# SCH_clock1_2025-09-25.net
KiCad netlist of a schematic drawn in EasyEDA
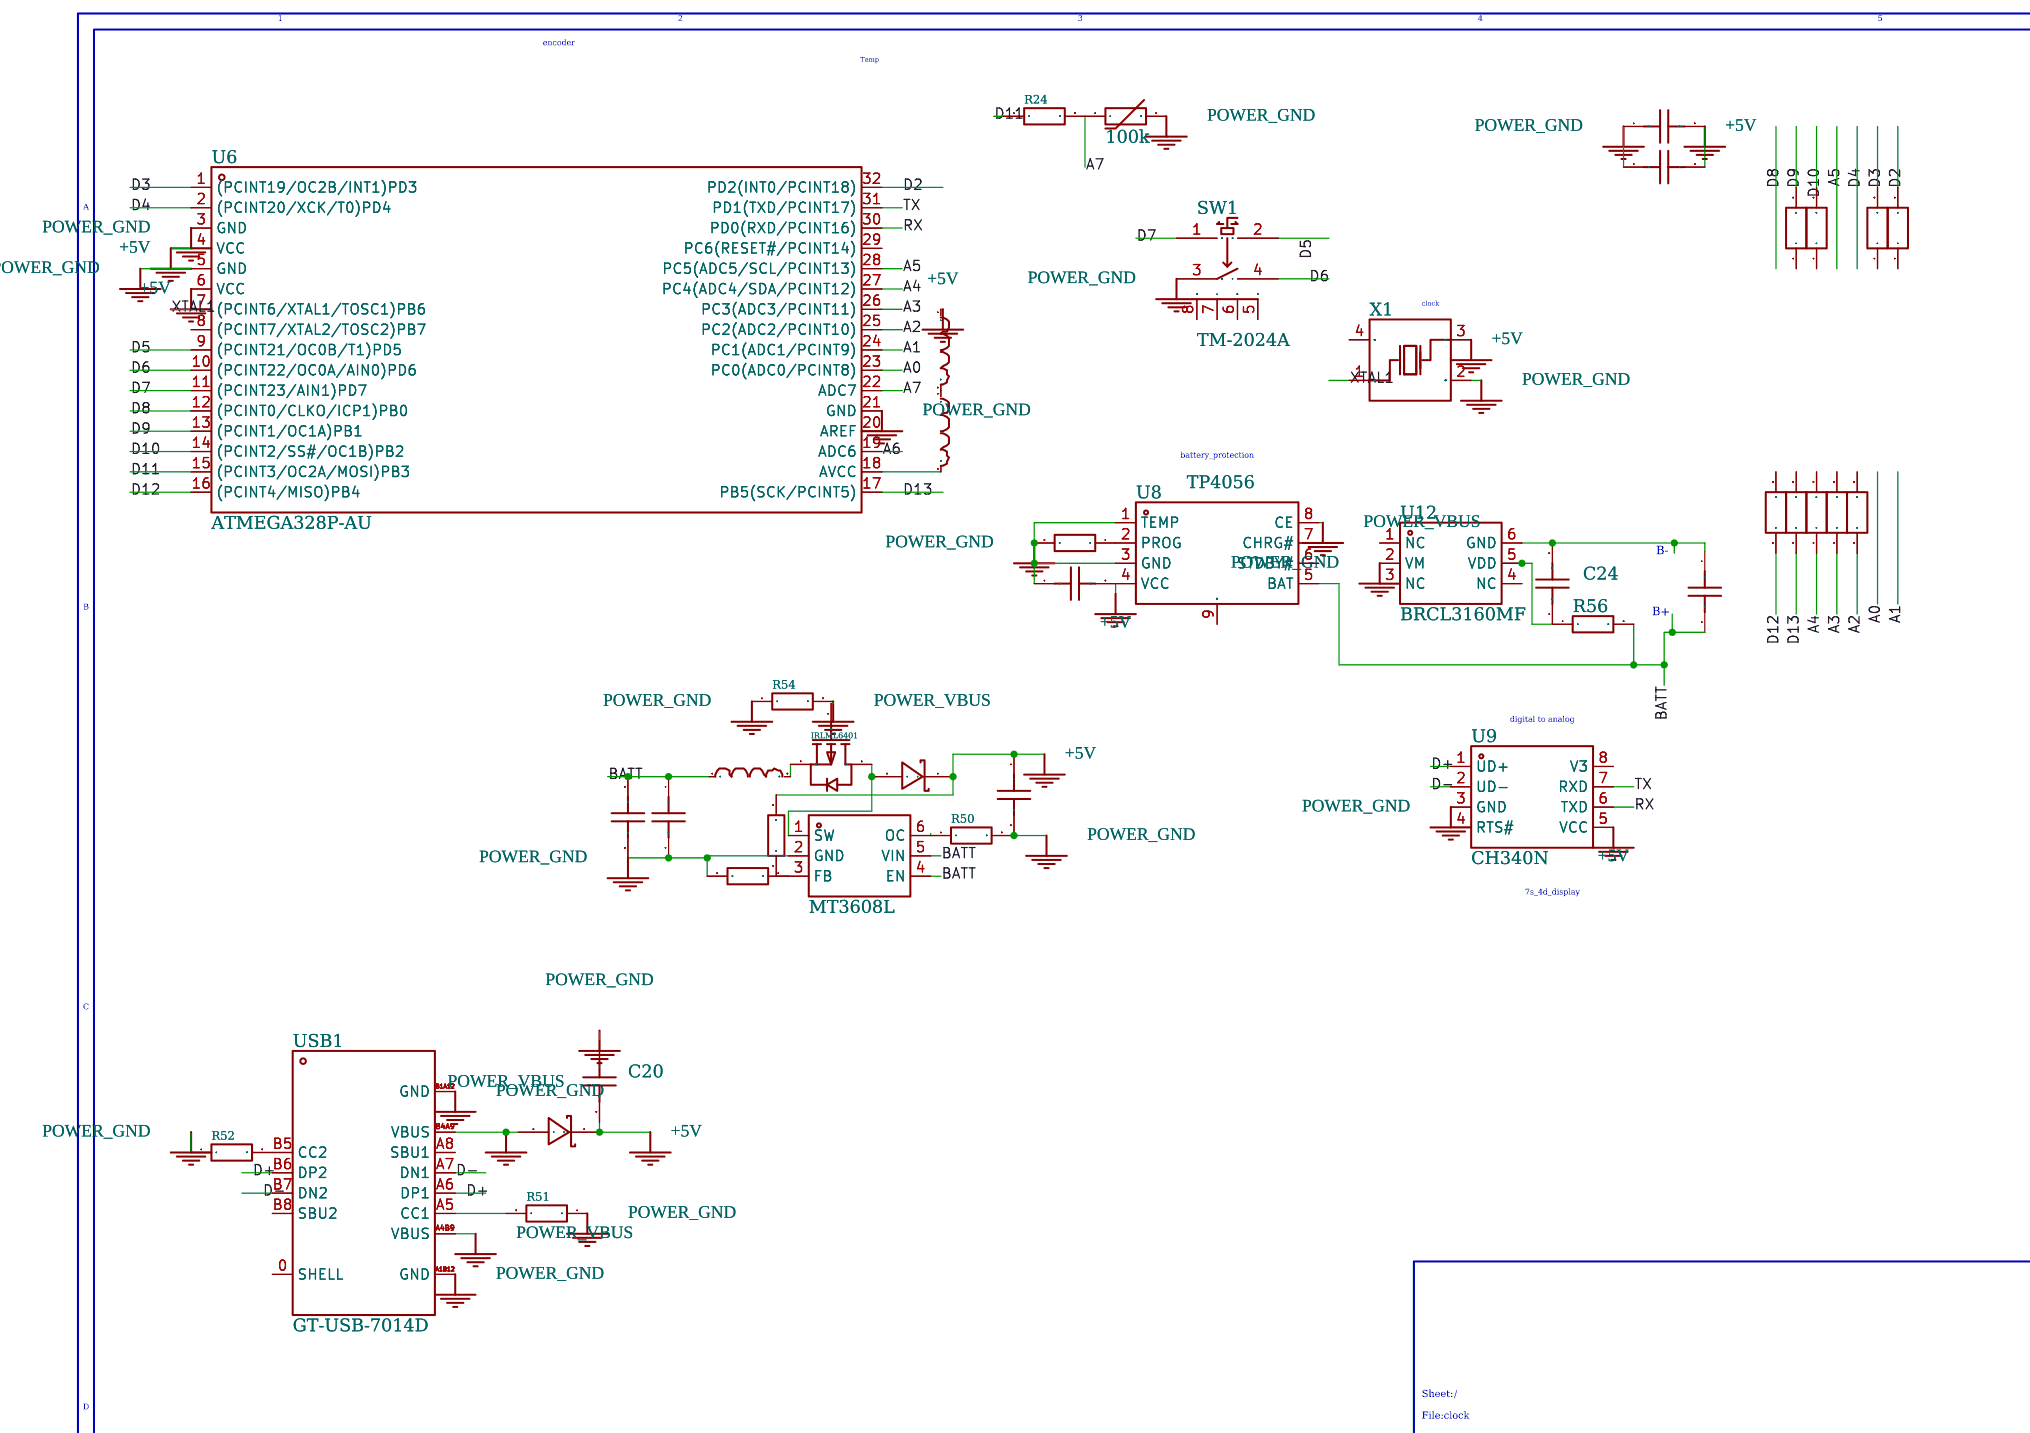
[diagram p0: schematic sheet]

(export (version "E")
  (design (tool "Eeschema 10.0.6"))
  (components
    (comp (ref "C15")
      (value "4.7uF")
      (fields
        (field (name "Manufacturer Part") "CL05A475MQ5NRNC")
        (field (name "Manufacturer") "SAMSUNG(三星)")
      )
      (libsource (lib "") (part "Unknown_300_-375"))
    )
    (comp (ref "C16")
      (value "4.7uF")
      (fields
        (field (name "Manufacturer Part") "CL05A475MQ5NRNC")
        (field (name "Manufacturer") "SAMSUNG(三星)")
      )
      (libsource (lib "") (part "Unknown_320_-375"))
    )
    (comp (ref "C19")
      (value "4.7uF")
      (fields
        (field (name "Manufacturer Part") "CL05A475MQ5NRNC")
        (field (name "Manufacturer") "SAMSUNG(三星)")
      )
      (libsource (lib "") (part "Unknown_520_-490"))
    )
    (comp (ref "C20")
      (value "4.7uF")
      (fields
        (field (name "Manufacturer Part") "CL05A475MQ5NRNC")
        (field (name "Manufacturer") "SAMSUNG(三星)")
      )
      (libsource (lib "") (part "Unknown_286_-245"))
    )
    (comp (ref "C21")
      (value "4.7uF")
      (fields
        (field (name "Manufacturer Part") "CL05A475MQ5NRNC")
        (field (name "Manufacturer") "SAMSUNG(三星)")
      )
      (libsource (lib "") (part "Unknown_490_-386"))
    )
    (comp (ref "C24")
      (value "100nF")
      (fields
        (field (name "Manufacturer Part") "FCC0402B104K160AT")
        (field (name "Manufacturer") "FOJAN(富捷)")
      )
      (libsource (lib "") (part "Unknown_755_-490"))
    )
    (comp (ref "C25")
      (value "4.7uF")
      (fields
        (field (name "Manufacturer Part") "CL05A475MQ5NRNC")
        (field (name "Manufacturer") "SAMSUNG(三星)")
      )
      (libsource (lib "") (part "Unknown_810_-715"))
    )
    (comp (ref "C27")
      (value "4.7uF")
      (fields
        (field (name "Manufacturer Part") "CL05A475MQ5NRNC")
        (field (name "Manufacturer") "SAMSUNG(三星)")
      )
      (libsource (lib "") (part "Unknown_810_-695"))
    )
    (comp (ref "C28")
      (value "4.7uF")
      (fields
        (field (name "Manufacturer Part") "CL05A475MQ5NRNC")
        (field (name "Manufacturer") "SAMSUNG(三星)")
      )
      (libsource (lib "") (part "Unknown_830_-486"))
    )
    (comp (ref "D5")
      (value "DSK34")
      (fields (field (name "Manufacturer") "MDD(辰达半导体)"))
      (libsource (lib "") (part "Unknown_440_-395"))
    )
    (comp (ref "D6")
      (value "DSK34")
      (fields (field (name "Manufacturer") "MDD(辰达半导体)"))
      (libsource (lib "") (part "Unknown_266_-220"))
    )
    (comp (ref "L3")
      (value "4.7uH")
      (fields (field (name "Manufacturer Part") "CMI321609U4R7KT") (field (name "Manufacturer") "FH(风华)"))
      (libsource (lib "") (part "Unknown_360_-395"))
    )
    (comp (ref "L5")
      (value "4.7uH")
      (fields (field (name "Manufacturer Part") "CMI321609U4R7KT") (field (name "Manufacturer") "FH(风华)"))
      (libsource (lib "") (part "Unknown_454_-565"))
    )
    (comp (ref "L6")
      (value "4.7uH")
      (fields (field (name "Manufacturer Part") "CMI321609U4R7KT") (field (name "Manufacturer") "FH(风华)"))
      (libsource (lib "") (part "Unknown_454_-605"))
    )
    (comp (ref "Q1")
      (value "IRLML6401")
      (fields (field (name "Manufacturer") "Hottech(合科泰)"))
      (libsource (lib "") (part "Unknown_400_-401"))
    )
    (comp (ref "R22")
      (value "100k")
      (fields (field (name "Manufacturer Part") "NCP03WF104F05RL") (field (name "Manufacturer") "muRata(村田)"))
      (libsource (lib "") (part "Unknown_545_-720"))
    )
    (comp (ref "R24")
      (value "100kΩ")
      (fields
        (field (name "Manufacturer Part") "0402WGF1003TCE")
        (field (name "Manufacturer") "UNI-ROYAL(厚声)")
      )
      (libsource (lib "") (part "Unknown_505_-720"))
    )
    (comp (ref "R39")
      (value "1kΩ")
      (fields (field (name "Manufacturer Part") "FRC0603F1001TS") (field (name "Manufacturer") "FOJAN(富捷)"))
      (libsource (lib "") (part "Unknown_875_-665"))
    )
    (comp (ref "R40")
      (value "1kΩ")
      (fields (field (name "Manufacturer Part") "FRC0603F1001TS") (field (name "Manufacturer") "FOJAN(富捷)"))
      (libsource (lib "") (part "Unknown_915_-665"))
    )
    (comp (ref "R41")
      (value "1kΩ")
      (fields (field (name "Manufacturer Part") "FRC0603F1001TS") (field (name "Manufacturer") "FOJAN(富捷)"))
      (libsource (lib "") (part "Unknown_885_-665"))
    )
    (comp (ref "R42")
      (value "1kΩ")
      (fields (field (name "Manufacturer Part") "FRC0603F1001TS") (field (name "Manufacturer") "FOJAN(富捷)"))
      (libsource (lib "") (part "Unknown_905_-525"))
    )
    (comp (ref "R43")
      (value "1kΩ")
      (fields (field (name "Manufacturer Part") "FRC0603F1001TS") (field (name "Manufacturer") "FOJAN(富捷)"))
      (libsource (lib "") (part "Unknown_895_-525"))
    )
    (comp (ref "R44")
      (value "1kΩ")
      (fields (field (name "Manufacturer Part") "FRC0603F1001TS") (field (name "Manufacturer") "FOJAN(富捷)"))
      (libsource (lib "") (part "Unknown_925_-665"))
    )
    (comp (ref "R45")
      (value "1kΩ")
      (fields (field (name "Manufacturer Part") "FRC0603F1001TS") (field (name "Manufacturer") "FOJAN(富捷)"))
      (libsource (lib "") (part "Unknown_875_-525"))
    )
    (comp (ref "R46")
      (value "1kΩ")
      (fields (field (name "Manufacturer Part") "FRC0603F1001TS") (field (name "Manufacturer") "FOJAN(富捷)"))
      (libsource (lib "") (part "Unknown_865_-525"))
    )
    (comp (ref "R48")
      (value "2.4kΩ")
      (fields
        (field (name "Manufacturer Part") "0402WGF2401TCE")
        (field (name "Manufacturer") "UNI-ROYAL(厚声)")
      )
      (libsource (lib "") (part "Unknown_520_-510"))
    )
    (comp (ref "R49")
      (value "2.4kΩ")
      (fields
        (field (name "Manufacturer Part") "0402WGF2401TCE")
        (field (name "Manufacturer") "UNI-ROYAL(厚声)")
      )
      (libsource (lib "") (part "Unknown_359_-346"))
    )
    (comp (ref "R50")
      (value "100kΩ")
      (fields
        (field (name "Manufacturer Part") "0402WGF1003TCE")
        (field (name "Manufacturer") "UNI-ROYAL(厚声)")
      )
      (libsource (lib "") (part "Unknown_469_-366"))
    )
    (comp (ref "R51")
      (value "5.1kΩ")
      (fields
        (field (name "Manufacturer Part") "0402WGF5101TCE")
        (field (name "Manufacturer") "UNI-ROYAL(厚声)")
      )
      (libsource (lib "") (part "Unknown_260_-180"))
    )
    (comp (ref "R52")
      (value "5.1kΩ")
      (fields
        (field (name "Manufacturer Part") "0402WGF5101TCE")
        (field (name "Manufacturer") "UNI-ROYAL(厚声)")
      )
      (libsource (lib "") (part "Unknown_105_-210"))
    )
    (comp (ref "R53")
      (value "20kΩ")
      (fields
        (field (name "Manufacturer Part") "0402WGF2002TCE")
        (field (name "Manufacturer") "UNI-ROYAL(厚声)")
      )
      (libsource (lib "") (part "Unknown_373_-366"))
    )
    (comp (ref "R54")
      (value "5.1kΩ")
      (fields
        (field (name "Manufacturer Part") "0402WGF5101TCE")
        (field (name "Manufacturer") "UNI-ROYAL(厚声)")
      )
      (libsource (lib "") (part "Unknown_381_-432"))
    )
    (comp (ref "R56")
      (value "100Ω")
      (fields
        (field (name "Manufacturer Part") "0402WGF1000TCE")
        (field (name "Manufacturer") "UNI-ROYAL(厚声)")
      )
      (libsource (lib "") (part "Unknown_775_-470"))
    )
    (comp (ref "R57")
      (value "1kΩ")
      (fields (field (name "Manufacturer Part") "FRC0603F1001TS") (field (name "Manufacturer") "FOJAN(富捷)"))
      (libsource (lib "") (part "Unknown_885_-525"))
    )
    (comp (ref "SW1")
      (value "TM-2024A")
      (fields (field (name "Manufacturer") "XKB Connection(中国星坤)"))
      (libsource (lib "") (part "Unknown_600_-640"))
    )
    (comp (ref "U6")
      (value "ATMEGA328P-AU")
      (fields (field (name "Manufacturer") "MICROCHIP(美国微芯)"))
      (libsource (lib "") (part "Unknown_255_-610"))
    )
    (comp (ref "U8")
      (value "TP4056")
      (fields (field (name "Manufacturer") "TDSEMIC(拓电半导体)"))
      (libsource (lib "") (part "Unknown_590_-505"))
    )
    (comp (ref "U9")
      (value "CH340N")
      (fields (field (name "Manufacturer") "WCH(南京沁恒)"))
      (libsource (lib "") (part "Unknown_745_-380"))
    )
    (comp (ref "U10")
      (value "MT3608L")
      (fields (field (name "Manufacturer") "西安航天民芯"))
      (libsource (lib "") (part "Unknown_414_-356"))
    )
    (comp (ref "U12")
      (value "BRCL3160MF")
      (fields (field (name "Manufacturer") "BLUE ROCKET(蓝箭)"))
      (libsource (lib "") (part "Unknown_705_-500"))
    )
    (comp (ref "USB1")
      (value "GT-USB-7014D")
      (fields (field (name "Manufacturer") "G-Switch(品赞)"))
      (libsource (lib "") (part "Unknown_175_-190"))
    )
    (comp (ref "X1")
      (value "16MHz")
      (fields (field (name "Manufacturer Part") "TAXM16M4RLBCCT2T") (field (name "Manufacturer") "YJX(雅晶鑫)"))
      (libsource (lib "") (part "Unknown_685_-600"))
    )
  )
  (nets
    (net (code "1") (name "+5V") (class "Default")
      (node (ref "C19") (pin "2") (pinfunction "2_2") (pintype "unspecified"))
      (node (ref "C20") (pin "2") (pinfunction "2_2") (pintype "unspecified"))
      (node (ref "C21") (pin "1") (pinfunction "1_1") (pintype "unspecified"))
      (node (ref "C25") (pin "2") (pinfunction "2_2") (pintype "unspecified"))
      (node (ref "C27") (pin "2") (pinfunction "2_2") (pintype "unspecified"))
      (node (ref "D5") (pin "1") (pinfunction "K_1") (pintype "unspecified"))
      (node (ref "D6") (pin "1") (pinfunction "K_1") (pintype "unspecified"))
      (node (ref "L6") (pin "1") (pinfunction "1_1") (pintype "unspecified"))
      (node (ref "R53") (pin "2") (pinfunction "2_2") (pintype "unspecified"))
      (node (ref "U6") (pin "4") (pinfunction "VCC_4") (pintype "unspecified"))
      (node (ref "U6") (pin "6") (pinfunction "VCC_6") (pintype "unspecified"))
      (node (ref "U8") (pin "4") (pinfunction "VCC_4") (pintype "unspecified"))
      (node (ref "U9") (pin "5") (pinfunction "VCC_5") (pintype "unspecified"))
      (node (ref "X1") (pin "3") (pinfunction "OSC2_3") (pintype "unspecified"))
    )
    (net (code "2") (name "/A0") (class "Default")
      (node (ref "U6") (pin "23") (pinfunction "PC0(ADC0/PCINT8)_23") (pintype "unspecified"))
    )
    (net (code "3") (name "/A1") (class "Default")
      (node (ref "U6") (pin "24") (pinfunction "PC1(ADC1/PCINT9)_24") (pintype "unspecified"))
    )
    (net (code "4") (name "/A2") (class "Default")
      (node (ref "R42") (pin "1") (pinfunction "1_1") (pintype "unspecified"))
      (node (ref "U6") (pin "25") (pinfunction "PC2(ADC2/PCINT10)_25") (pintype "unspecified"))
    )
    (net (code "5") (name "/A3") (class "Default")
      (node (ref "R43") (pin "1") (pinfunction "1_1") (pintype "unspecified"))
      (node (ref "U6") (pin "26") (pinfunction "PC3(ADC3/PCINT11)_26") (pintype "unspecified"))
    )
    (net (code "6") (name "/A4") (class "Default")
      (node (ref "R57") (pin "1") (pinfunction "1_1") (pintype "unspecified"))
      (node (ref "U6") (pin "27") (pinfunction "PC4(ADC4/SDA/PCINT12)_27") (pintype "unspecified"))
    )
    (net (code "7") (name "/A5") (class "Default")
      (node (ref "U6") (pin "28") (pinfunction "PC5(ADC5/SCL/PCINT13)_28") (pintype "unspecified"))
    )
    (net (code "8") (name "/A6") (class "Default")
      (node (ref "U6") (pin "19") (pinfunction "ADC6_19") (pintype "unspecified"))
    )
    (net (code "9") (name "/A7") (class "Default")
      (node (ref "R22") (pin "1") (pinfunction "1_1") (pintype "unspecified"))
      (node (ref "R24") (pin "2") (pinfunction "2_2") (pintype "unspecified"))
      (node (ref "U6") (pin "22") (pinfunction "ADC7_22") (pintype "unspecified"))
    )
    (net (code "10") (name "/BATT") (class "Default")
      (node (ref "C15") (pin "1") (pinfunction "1_1") (pintype "unspecified"))
      (node (ref "C16") (pin "1") (pinfunction "1_1") (pintype "unspecified"))
      (node (ref "C28") (pin "2") (pinfunction "2_2") (pintype "unspecified"))
      (node (ref "L3") (pin "1") (pinfunction "1_1") (pintype "unspecified"))
      (node (ref "R56") (pin "2") (pinfunction "2_2") (pintype "unspecified"))
      (node (ref "U10") (pin "4") (pinfunction "EN_4") (pintype "unspecified"))
      (node (ref "U10") (pin "5") (pinfunction "VIN_5") (pintype "unspecified"))
      (node (ref "U8") (pin "5") (pinfunction "BAT_5") (pintype "unspecified"))
    )
    (net (code "11") (name "/D+") (class "Default")
      (node (ref "U9") (pin "1") (pinfunction "UD+_1") (pintype "unspecified"))
      (node (ref "USB1") (pin "A6") (pinfunction "DP1_A6") (pintype "unspecified"))
      (node (ref "USB1") (pin "B6") (pinfunction "DP2_B6") (pintype "unspecified"))
    )
    (net (code "12") (name "/D-") (class "Default")
      (node (ref "U9") (pin "2") (pinfunction "UD-_2") (pintype "unspecified"))
      (node (ref "USB1") (pin "A7") (pinfunction "DN1_A7") (pintype "unspecified"))
      (node (ref "USB1") (pin "B7") (pinfunction "DN2_B7") (pintype "unspecified"))
    )
    (net (code "13") (name "/D2") (class "Default")
      (node (ref "R44") (pin "2") (pinfunction "2_2") (pintype "unspecified"))
      (node (ref "U6") (pin "32") (pinfunction "PD2(INT0/PCINT18)_32") (pintype "unspecified"))
    )
    (net (code "14") (name "/D3") (class "Default")
      (node (ref "R40") (pin "2") (pinfunction "2_2") (pintype "unspecified"))
      (node (ref "U6") (pin "1") (pinfunction "(PCINT19/OC2B/INT1)PD3_1") (pintype "unspecified"))
    )
    (net (code "15") (name "/D4") (class "Default")
      (node (ref "U6") (pin "2") (pinfunction "(PCINT20/XCK/T0)PD4_2") (pintype "unspecified"))
    )
    (net (code "16") (name "/D5") (class "Default")
      (node (ref "SW1") (pin "2") (pinfunction "2_2") (pintype "unspecified"))
      (node (ref "U6") (pin "9") (pinfunction "(PCINT21/OC0B/T1)PD5_9") (pintype "unspecified"))
    )
    (net (code "17") (name "/D6") (class "Default")
      (node (ref "SW1") (pin "4") (pinfunction "4_4") (pintype "unspecified"))
      (node (ref "U6") (pin "10") (pinfunction "(PCINT22/OC0A/AIN0)PD6_10") (pintype "unspecified"))
    )
    (net (code "18") (name "/D7") (class "Default")
      (node (ref "SW1") (pin "1") (pinfunction "1_1") (pintype "unspecified"))
      (node (ref "U6") (pin "11") (pinfunction "(PCINT23/AIN1)PD7_11") (pintype "unspecified"))
    )
    (net (code "19") (name "/D8") (class "Default")
      (node (ref "U6") (pin "12") (pinfunction "(PCINT0/CLKO/ICP1)PB0_12") (pintype "unspecified"))
    )
    (net (code "20") (name "/D9") (class "Default")
      (node (ref "R39") (pin "2") (pinfunction "2_2") (pintype "unspecified"))
      (node (ref "U6") (pin "13") (pinfunction "(PCINT1/OC1A)PB1_13") (pintype "unspecified"))
    )
    (net (code "21") (name "/D10") (class "Default")
      (node (ref "R41") (pin "2") (pinfunction "2_2") (pintype "unspecified"))
      (node (ref "U6") (pin "14") (pinfunction "(PCINT2/SS#/OC1B)PB2_14") (pintype "unspecified"))
    )
    (net (code "22") (name "/D11") (class "Default")
      (node (ref "R24") (pin "1") (pinfunction "1_1") (pintype "unspecified"))
      (node (ref "U6") (pin "15") (pinfunction "(PCINT3/OC2A/MOSI)PB3_15") (pintype "unspecified"))
    )
    (net (code "23") (name "/D12") (class "Default")
      (node (ref "R46") (pin "1") (pinfunction "1_1") (pintype "unspecified"))
      (node (ref "U6") (pin "16") (pinfunction "(PCINT4/MISO)PB4_16") (pintype "unspecified"))
    )
    (net (code "24") (name "/D13") (class "Default")
      (node (ref "R45") (pin "1") (pinfunction "1_1") (pintype "unspecified"))
      (node (ref "U6") (pin "17") (pinfunction "PB5(SCK/PCINT5)_17") (pintype "unspecified"))
    )
    (net (code "25") (name "/RX") (class "Default")
      (node (ref "U6") (pin "30") (pinfunction "PD0(RXD/PCINT16)_30") (pintype "unspecified"))
      (node (ref "U9") (pin "6") (pinfunction "TXD_6") (pintype "unspecified"))
    )
    (net (code "26") (name "/TX") (class "Default")
      (node (ref "U6") (pin "31") (pinfunction "PD1(TXD/PCINT17)_31") (pintype "unspecified"))
      (node (ref "U9") (pin "7") (pinfunction "RXD_7") (pintype "unspecified"))
    )
    (net (code "27") (name "/XTAL1") (class "Default")
      (node (ref "U6") (pin "7") (pinfunction "(PCINT6/XTAL1/TOSC1)PB6_7") (pintype "unspecified"))
      (node (ref "X1") (pin "1") (pinfunction "OSC1_1") (pintype "unspecified"))
    )
    (net (code "28") (name "Net-(D5-A)") (class "Default")
      (node (ref "D5") (pin "2") (pinfunction "A_2") (pintype "unspecified"))
      (node (ref "Q1") (pin "3") (pinfunction "D_3") (pintype "unspecified"))
      (node (ref "U10") (pin "1") (pinfunction "SW_1") (pintype "unspecified"))
    )
    (net (code "29") (name "Net-(L5-Pad1)") (class "Default")
      (node (ref "L5") (pin "1") (pinfunction "1_1") (pintype "unspecified"))
      (node (ref "L6") (pin "2") (pinfunction "2_2") (pintype "unspecified"))
    )
    (net (code "30") (name "Net-(Q1-S)") (class "Default")
      (node (ref "L3") (pin "2") (pinfunction "2_2") (pintype "unspecified"))
      (node (ref "Q1") (pin "2") (pinfunction "S_2") (pintype "unspecified"))
    )
    (net (code "31") (name "Net-(U6-AVCC)") (class "Default")
      (node (ref "L5") (pin "2") (pinfunction "2_2") (pintype "unspecified"))
      (node (ref "U6") (pin "18") (pinfunction "AVCC_18") (pintype "unspecified"))
    )
    (net (code "32") (name "Net-(U8-PROG)") (class "Default")
      (node (ref "R48") (pin "1") (pinfunction "1_1") (pintype "unspecified"))
      (node (ref "U8") (pin "2") (pinfunction "PROG_2") (pintype "unspecified"))
    )
    (net (code "33") (name "Net-(U10-FB)") (class "Default")
      (node (ref "R49") (pin "1") (pinfunction "1_1") (pintype "unspecified"))
      (node (ref "R53") (pin "1") (pinfunction "1_1") (pintype "unspecified"))
      (node (ref "U10") (pin "3") (pinfunction "FB_3") (pintype "unspecified"))
    )
    (net (code "34") (name "Net-(U10-OC)") (class "Default")
      (node (ref "R50") (pin "1") (pinfunction "1_1") (pintype "unspecified"))
      (node (ref "U10") (pin "6") (pinfunction "OC_6") (pintype "unspecified"))
    )
    (net (code "35") (name "Net-(U12-GND)") (class "Default")
      (node (ref "C24") (pin "2") (pinfunction "2_2") (pintype "unspecified"))
      (node (ref "C28") (pin "1") (pinfunction "1_1") (pintype "unspecified"))
      (node (ref "U12") (pin "6") (pinfunction "GND_6") (pintype "unspecified"))
    )
    (net (code "36") (name "Net-(U12-VDD)") (class "Default")
      (node (ref "C24") (pin "1") (pinfunction "1_1") (pintype "unspecified"))
      (node (ref "R56") (pin "1") (pinfunction "1_1") (pintype "unspecified"))
      (node (ref "U12") (pin "5") (pinfunction "VDD_5") (pintype "unspecified"))
    )
    (net (code "37") (name "Net-(USB1-CC1)") (class "Default")
      (node (ref "R51") (pin "2") (pinfunction "2_2") (pintype "unspecified"))
      (node (ref "USB1") (pin "A5") (pinfunction "CC1_A5") (pintype "unspecified"))
    )
    (net (code "38") (name "Net-(USB1-CC2)") (class "Default")
      (node (ref "R52") (pin "2") (pinfunction "2_2") (pintype "unspecified"))
      (node (ref "USB1") (pin "B5") (pinfunction "CC2_B5") (pintype "unspecified"))
    )
    (net (code "39") (name "POWER_GND") (class "Default")
      (node (ref "C15") (pin "2") (pinfunction "2_2") (pintype "unspecified"))
      (node (ref "C16") (pin "2") (pinfunction "2_2") (pintype "unspecified"))
      (node (ref "C19") (pin "1") (pinfunction "1_1") (pintype "unspecified"))
      (node (ref "C20") (pin "1") (pinfunction "1_1") (pintype "unspecified"))
      (node (ref "C21") (pin "2") (pinfunction "2_2") (pintype "unspecified"))
      (node (ref "C25") (pin "1") (pinfunction "1_1") (pintype "unspecified"))
      (node (ref "C27") (pin "1") (pinfunction "1_1") (pintype "unspecified"))
      (node (ref "R22") (pin "2") (pinfunction "2_2") (pintype "unspecified"))
      (node (ref "R48") (pin "2") (pinfunction "2_2") (pintype "unspecified"))
      (node (ref "R49") (pin "2") (pinfunction "2_2") (pintype "unspecified"))
      (node (ref "R50") (pin "2") (pinfunction "2_2") (pintype "unspecified"))
      (node (ref "R51") (pin "1") (pinfunction "1_1") (pintype "unspecified"))
      (node (ref "R52") (pin "1") (pinfunction "1_1") (pintype "unspecified"))
      (node (ref "R54") (pin "1") (pinfunction "1_1") (pintype "unspecified"))
      (node (ref "SW1") (pin "3") (pinfunction "3_3") (pintype "unspecified"))
      (node (ref "U10") (pin "2") (pinfunction "GND_2") (pintype "unspecified"))
      (node (ref "U12") (pin "2") (pinfunction "VM_2") (pintype "unspecified"))
      (node (ref "U6") (pin "21") (pinfunction "GND_21") (pintype "unspecified"))
      (node (ref "U6") (pin "3") (pinfunction "GND_3") (pintype "unspecified"))
      (node (ref "U6") (pin "5") (pinfunction "GND_5") (pintype "unspecified"))
      (node (ref "U8") (pin "1") (pinfunction "TEMP_1") (pintype "unspecified"))
      (node (ref "U8") (pin "3") (pinfunction "GND_3") (pintype "unspecified"))
      (node (ref "U9") (pin "3") (pinfunction "GND_3") (pintype "unspecified"))
      (node (ref "USB1") (pin "A1B12") (pinfunction "GND_A1B12") (pintype "unspecified"))
      (node (ref "USB1") (pin "B1A12") (pinfunction "GND_B1A12") (pintype "unspecified"))
      (node (ref "X1") (pin "2") (pinfunction "GND_2") (pintype "unspecified"))
    )
    (net (code "40") (name "POWER_VBUS") (class "Default")
      (node (ref "D6") (pin "2") (pinfunction "A_2") (pintype "unspecified"))
      (node (ref "Q1") (pin "1") (pinfunction "G_1") (pintype "unspecified"))
      (node (ref "R54") (pin "2") (pinfunction "2_2") (pintype "unspecified"))
      (node (ref "U8") (pin "8") (pinfunction "CE_8") (pintype "unspecified"))
      (node (ref "USB1") (pin "A4B9") (pinfunction "VBUS_A4B9") (pintype "unspecified"))
      (node (ref "USB1") (pin "B4A9") (pinfunction "VBUS_B4A9") (pintype "unspecified"))
    )
    (net (code "41") (name "unconnected-(R39-Pad1)") (class "Default")
      (node (ref "R39") (pin "1") (pinfunction "1_1") (pintype "unspecified"))
    )
    (net (code "42") (name "unconnected-(R40-Pad1)") (class "Default")
      (node (ref "R40") (pin "1") (pinfunction "1_1") (pintype "unspecified"))
    )
    (net (code "43") (name "unconnected-(R41-Pad1)") (class "Default")
      (node (ref "R41") (pin "1") (pinfunction "1_1") (pintype "unspecified"))
    )
    (net (code "44") (name "unconnected-(R42-Pad2)") (class "Default")
      (node (ref "R42") (pin "2") (pinfunction "2_2") (pintype "unspecified"))
    )
    (net (code "45") (name "unconnected-(R43-Pad2)") (class "Default")
      (node (ref "R43") (pin "2") (pinfunction "2_2") (pintype "unspecified"))
    )
    (net (code "46") (name "unconnected-(R44-Pad1)") (class "Default")
      (node (ref "R44") (pin "1") (pinfunction "1_1") (pintype "unspecified"))
    )
    (net (code "47") (name "unconnected-(R45-Pad2)") (class "Default")
      (node (ref "R45") (pin "2") (pinfunction "2_2") (pintype "unspecified"))
    )
    (net (code "48") (name "unconnected-(R46-Pad2)") (class "Default")
      (node (ref "R46") (pin "2") (pinfunction "2_2") (pintype "unspecified"))
    )
    (net (code "49") (name "unconnected-(R57-Pad2)") (class "Default")
      (node (ref "R57") (pin "2") (pinfunction "2_2") (pintype "unspecified"))
    )
    (net (code "50") (name "unconnected-(SW1-Pad5)") (class "Default")
      (node (ref "SW1") (pin "5") (pinfunction "5_5") (pintype "unspecified"))
    )
    (net (code "51") (name "unconnected-(SW1-Pad6)") (class "Default")
      (node (ref "SW1") (pin "6") (pinfunction "6_6") (pintype "unspecified"))
    )
    (net (code "52") (name "unconnected-(SW1-Pad7)") (class "Default")
      (node (ref "SW1") (pin "7") (pinfunction "7_7") (pintype "unspecified"))
    )
    (net (code "53") (name "unconnected-(SW1-Pad8)") (class "Default")
      (node (ref "SW1") (pin "8") (pinfunction "8_8") (pintype "unspecified"))
    )
    (net (code "54") (name "unconnected-(U6-(PCINT7{slash}XTAL2{slash}TOSC2)PB7-Pad8)") (class "Default")
      (node (ref "U6") (pin "8") (pinfunction "(PCINT7/XTAL2/TOSC2)PB7_8") (pintype "unspecified"))
    )
    (net (code "55") (name "unconnected-(U6-AREF-Pad20)") (class "Default")
      (node (ref "U6") (pin "20") (pinfunction "AREF_20") (pintype "unspecified"))
    )
    (net (code "56") (name "unconnected-(U6-PC6(RESET#{slash}PCINT14)-Pad29)") (class "Default")
      (node (ref "U6") (pin "29") (pinfunction "PC6(RESET#/PCINT14)_29") (pintype "unspecified"))
    )
    (net (code "57") (name "unconnected-(U8-CHRG#-Pad7)") (class "Default")
      (node (ref "U8") (pin "7") (pinfunction "CHRG#_7") (pintype "unspecified"))
    )
    (net (code "58") (name "unconnected-(U8-GND-Pad9)") (class "Default")
      (node (ref "U8") (pin "9") (pinfunction "GND_9") (pintype "unspecified"))
    )
    (net (code "59") (name "unconnected-(U8-STDBY#-Pad6)") (class "Default")
      (node (ref "U8") (pin "6") (pinfunction "STDBY#_6") (pintype "unspecified"))
    )
    (net (code "60") (name "unconnected-(U9-RTS#-Pad4)") (class "Default")
      (node (ref "U9") (pin "4") (pinfunction "RTS#_4") (pintype "unspecified"))
    )
    (net (code "61") (name "unconnected-(U9-V3-Pad8)") (class "Default")
      (node (ref "U9") (pin "8") (pinfunction "V3_8") (pintype "unspecified"))
    )
    (net (code "62") (name "unconnected-(U12-NC-Pad1)") (class "Default")
      (node (ref "U12") (pin "1") (pinfunction "NC_1") (pintype "unspecified"))
    )
    (net (code "63") (name "unconnected-(U12-NC-Pad3)") (class "Default")
      (node (ref "U12") (pin "3") (pinfunction "NC_3") (pintype "unspecified"))
    )
    (net (code "64") (name "unconnected-(U12-NC-Pad4)") (class "Default")
      (node (ref "U12") (pin "4") (pinfunction "NC_4") (pintype "unspecified"))
    )
    (net (code "65") (name "unconnected-(USB1-SBU1-PadA8)") (class "Default")
      (node (ref "USB1") (pin "A8") (pinfunction "SBU1_A8") (pintype "unspecified"))
    )
    (net (code "66") (name "unconnected-(USB1-SBU2-PadB8)") (class "Default")
      (node (ref "USB1") (pin "B8") (pinfunction "SBU2_B8") (pintype "unspecified"))
    )
    (net (code "67") (name "unconnected-(USB1-SHELL-Pad0)") (class "Default")
      (node (ref "USB1") (pin "0") (pinfunction "SHELL_0") (pintype "unspecified"))
    )
    (net (code "68") (name "unconnected-(X1-GND-Pad4)") (class "Default")
      (node (ref "X1") (pin "4") (pinfunction "GND_4") (pintype "unspecified"))
    )
  )
)
